# koszulka_led.net
KiCad netlist of a schematic drawn in EAGLE
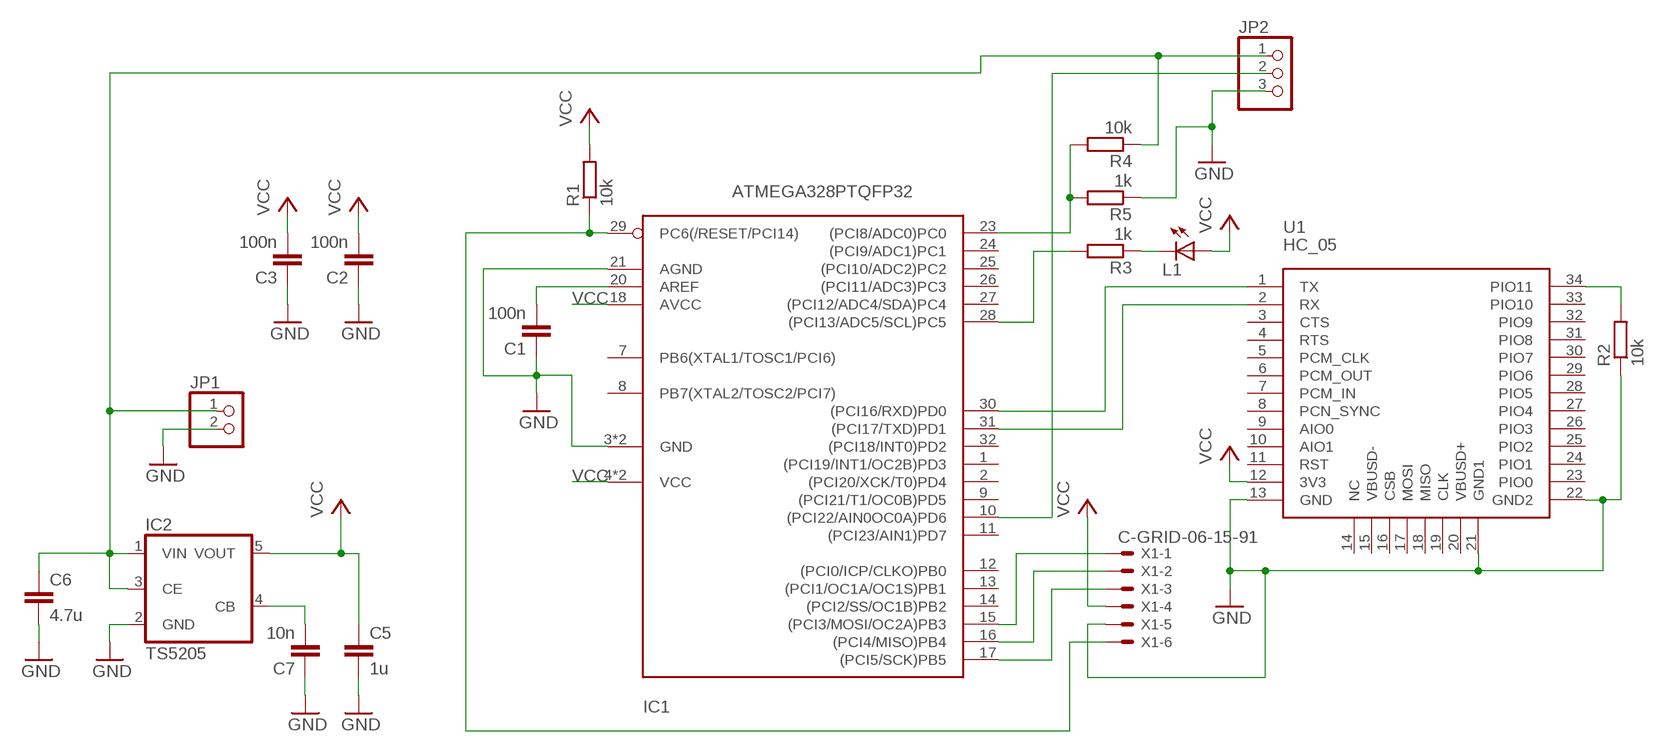
[diagram p0: schematic, sheet 1]

(export (version "E")
  (design (tool "Eeschema 10.0.6"))
  (components
    (comp (ref "C1")
      (value "100n")
      (footprint "eagle-import:C0402")
      (libsource (lib "eagle-import") (part "C-EUC0402"))
    )
    (comp (ref "C2")
      (value "100n")
      (footprint "eagle-import:C0402")
      (libsource (lib "eagle-import") (part "C-EUC0402"))
    )
    (comp (ref "C3")
      (value "100n")
      (footprint "eagle-import:C0402")
      (libsource (lib "eagle-import") (part "C-EUC0402"))
    )
    (comp (ref "C5")
      (value "1u")
      (footprint "eagle-import:C0805")
      (libsource (lib "eagle-import") (part "C-EUC0805"))
    )
    (comp (ref "C6")
      (value "4.7u")
      (footprint "eagle-import:C0805")
      (libsource (lib "eagle-import") (part "C-EUC0805"))
    )
    (comp (ref "C7")
      (value "10n")
      (footprint "eagle-import:C0402")
      (libsource (lib "eagle-import") (part "C-EUC0402"))
    )
    (comp (ref "IC1")
      (value "ATMEGA328PTQFP32")
      (footprint "eagle-import:TQFP32-08")
      (libsource (lib "eagle-import") (part "ATMEGA328PTQFP32"))
    )
    (comp (ref "IC2")
      (value "TS5205")
      (footprint "eagle-import:SOT25")
      (libsource (lib "eagle-import") (part "TS5205"))
    )
    (comp (ref "JP1")
      (value "PINHD-1X2")
      (footprint "eagle-import:1X02")
      (libsource (lib "eagle-import") (part "PINHD-1X2"))
    )
    (comp (ref "JP2")
      (value "PINHD-1X3")
      (footprint "eagle-import:1X03")
      (libsource (lib "eagle-import") (part "PINHD-1X3"))
    )
    (comp (ref "L1")
      (value "LEDCHIP-LED0603")
      (footprint "eagle-import:CHIP-LED0603")
      (libsource (lib "eagle-import") (part "LEDCHIP-LED0603"))
    )
    (comp (ref "R1")
      (value "10k")
      (footprint "eagle-import:R0603")
      (libsource (lib "eagle-import") (part "R-EU_R0603"))
    )
    (comp (ref "R2")
      (value "10k")
      (footprint "eagle-import:R0603")
      (libsource (lib "eagle-import") (part "R-EU_R0603"))
    )
    (comp (ref "R3")
      (value "1k")
      (footprint "eagle-import:R0603")
      (libsource (lib "eagle-import") (part "R-EU_R0603"))
    )
    (comp (ref "R4")
      (value "10k")
      (footprint "eagle-import:R0603")
      (libsource (lib "eagle-import") (part "R-EU_R0603"))
    )
    (comp (ref "R5")
      (value "1k")
      (footprint "eagle-import:R0603")
      (libsource (lib "eagle-import") (part "R-EU_R0603"))
    )
    (comp (ref "U1")
      (value "HC_05")
      (footprint "eagle-import:BLUETOOTH_SMD")
      (libsource (lib "eagle-import") (part "HC_05"))
    )
    (comp (ref "X1")
      (value "C-GRID-06-15-91")
      (footprint "eagle-import:15-91-06")
      (libsource (lib "eagle-import") (part "C-GRID-06-15-91"))
    )
  )
  (nets
    (net (code "1") (name "GND") (class "Default")
      (node (ref "C1") (pin "1") (pinfunction "1_1") (pintype "passive"))
      (node (ref "C2") (pin "1") (pinfunction "1_1") (pintype "passive"))
      (node (ref "C3") (pin "1") (pinfunction "1_1") (pintype "passive"))
      (node (ref "C5") (pin "2") (pinfunction "2_2") (pintype "passive"))
      (node (ref "C6") (pin "2") (pinfunction "2_2") (pintype "passive"))
      (node (ref "C7") (pin "1") (pinfunction "1_1") (pintype "passive"))
      (node (ref "IC1") (pin "21") (pinfunction "AGND_21") (pintype "bidirectional"))
      (node (ref "IC1") (pin "3") (pinfunction "GND_3") (pintype "bidirectional"))
      (node (ref "IC1") (pin "5") (pinfunction "GND_5") (pintype "bidirectional"))
      (node (ref "IC2") (pin "2") (pinfunction "GND_2") (pintype "passive"))
      (node (ref "JP1") (pin "2") (pinfunction "2_2") (pintype "passive"))
      (node (ref "JP2") (pin "3") (pinfunction "3_3") (pintype "passive"))
      (node (ref "R2") (pin "1") (pinfunction "1_1") (pintype "passive"))
      (node (ref "R5") (pin "1") (pinfunction "1_1") (pintype "passive"))
      (node (ref "U1") (pin "13") (pinfunction "GND_13") (pintype "bidirectional"))
      (node (ref "U1") (pin "21") (pinfunction "GND1_21") (pintype "bidirectional"))
      (node (ref "U1") (pin "22") (pinfunction "GND2_22") (pintype "bidirectional"))
      (node (ref "X1") (pin "5") (pinfunction "S_5") (pintype "passive"))
    )
    (net (code "2") (name "Net-(IC1-(PCI3{slash}MOSI{slash}OC2A)PB3)") (class "Default")
      (node (ref "IC1") (pin "15") (pinfunction "(PCI3/MOSI/OC2A)PB3_15") (pintype "bidirectional"))
      (node (ref "X1") (pin "1") (pinfunction "S_1") (pintype "passive"))
    )
    (net (code "3") (name "Net-(IC1-(PCI4{slash}MISO)PB4)") (class "Default")
      (node (ref "IC1") (pin "16") (pinfunction "(PCI4/MISO)PB4_16") (pintype "bidirectional"))
      (node (ref "X1") (pin "2") (pinfunction "S_2") (pintype "passive"))
    )
    (net (code "4") (name "Net-(IC1-(PCI5{slash}SCK)PB5)") (class "Default")
      (node (ref "IC1") (pin "17") (pinfunction "(PCI5/SCK)PB5_17") (pintype "bidirectional"))
      (node (ref "X1") (pin "3") (pinfunction "S_3") (pintype "passive"))
    )
    (net (code "5") (name "Net-(IC1-(PCI8{slash}ADC0)PC0)") (class "Default")
      (node (ref "IC1") (pin "23") (pinfunction "(PCI8/ADC0)PC0_23") (pintype "bidirectional"))
      (node (ref "R4") (pin "2") (pinfunction "2_2") (pintype "passive"))
      (node (ref "R5") (pin "2") (pinfunction "2_2") (pintype "passive"))
    )
    (net (code "6") (name "Net-(IC1-(PCI13{slash}ADC5{slash}SCL)PC5)") (class "Default")
      (node (ref "IC1") (pin "28") (pinfunction "(PCI13/ADC5/SCL)PC5_28") (pintype "bidirectional"))
      (node (ref "R3") (pin "2") (pinfunction "2_2") (pintype "passive"))
    )
    (net (code "7") (name "Net-(IC1-(PCI16{slash}RXD)PD0)") (class "Default")
      (node (ref "IC1") (pin "30") (pinfunction "(PCI16/RXD)PD0_30") (pintype "bidirectional"))
      (node (ref "U1") (pin "1") (pinfunction "TX_1") (pintype "bidirectional"))
    )
    (net (code "8") (name "Net-(IC1-(PCI17{slash}TXD)PD1)") (class "Default")
      (node (ref "IC1") (pin "31") (pinfunction "(PCI17/TXD)PD1_31") (pintype "bidirectional"))
      (node (ref "U1") (pin "2") (pinfunction "RX_2") (pintype "bidirectional"))
    )
    (net (code "9") (name "Net-(IC1-(PCI22{slash}AIN0OC0A)PD6)") (class "Default")
      (node (ref "IC1") (pin "10") (pinfunction "(PCI22/AIN0OC0A)PD6_10") (pintype "bidirectional"))
      (node (ref "JP2") (pin "2") (pinfunction "2_2") (pintype "passive"))
    )
    (net (code "10") (name "Net-(IC1-AREF)") (class "Default")
      (node (ref "C1") (pin "2") (pinfunction "2_2") (pintype "passive"))
      (node (ref "IC1") (pin "20") (pinfunction "AREF_20") (pintype "bidirectional"))
    )
    (net (code "11") (name "Net-(IC1-PC6({slash}RESET{slash}PCI14))") (class "Default")
      (node (ref "IC1") (pin "29") (pinfunction "PC6(/RESET/PCI14)_29") (pintype "bidirectional"))
      (node (ref "R1") (pin "1") (pinfunction "1_1") (pintype "passive"))
      (node (ref "X1") (pin "6") (pinfunction "S_6") (pintype "passive"))
    )
    (net (code "12") (name "Net-(IC2-CB)") (class "Default")
      (node (ref "C7") (pin "2") (pinfunction "2_2") (pintype "passive"))
      (node (ref "IC2") (pin "4") (pinfunction "CB_4") (pintype "input"))
    )
    (net (code "13") (name "Net-(IC2-CE)") (class "Default")
      (node (ref "C6") (pin "1") (pinfunction "1_1") (pintype "passive"))
      (node (ref "IC2") (pin "1") (pinfunction "VIN_1") (pintype "input"))
      (node (ref "IC2") (pin "3") (pinfunction "CE_3") (pintype "input"))
      (node (ref "JP1") (pin "1") (pinfunction "1_1") (pintype "passive"))
      (node (ref "JP2") (pin "1") (pinfunction "1_1") (pintype "passive"))
      (node (ref "R4") (pin "1") (pinfunction "1_1") (pintype "passive"))
    )
    (net (code "14") (name "Net-(L1-PadC)") (class "Default")
      (node (ref "L1") (pin "C") (pinfunction "C_C") (pintype "passive"))
      (node (ref "R3") (pin "1") (pinfunction "1_1") (pintype "passive"))
    )
    (net (code "15") (name "Net-(U1-PIO11)") (class "Default")
      (node (ref "R2") (pin "2") (pinfunction "2_2") (pintype "passive"))
      (node (ref "U1") (pin "34") (pinfunction "PIO11_34") (pintype "bidirectional"))
    )
    (net (code "16") (name "VCC") (class "Default")
      (node (ref "C2") (pin "2") (pinfunction "2_2") (pintype "passive"))
      (node (ref "C3") (pin "2") (pinfunction "2_2") (pintype "passive"))
      (node (ref "C5") (pin "1") (pinfunction "1_1") (pintype "passive"))
      (node (ref "IC1") (pin "18") (pinfunction "AVCC_18") (pintype "bidirectional"))
      (node (ref "IC1") (pin "4") (pinfunction "VCC_4") (pintype "bidirectional"))
      (node (ref "IC1") (pin "6") (pinfunction "VCC_6") (pintype "bidirectional"))
      (node (ref "IC2") (pin "5") (pinfunction "VOUT_5") (pintype "passive"))
      (node (ref "L1") (pin "A") (pinfunction "A_A") (pintype "passive"))
      (node (ref "R1") (pin "2") (pinfunction "2_2") (pintype "passive"))
      (node (ref "U1") (pin "12") (pinfunction "3V3_12") (pintype "bidirectional"))
      (node (ref "X1") (pin "4") (pinfunction "S_4") (pintype "passive"))
    )
    (net (code "17") (name "unconnected-(IC1-(PCI0{slash}ICP{slash}CLKO)PB0-Pad12)") (class "Default")
      (node (ref "IC1") (pin "12") (pinfunction "(PCI0/ICP/CLKO)PB0_12") (pintype "bidirectional"))
    )
    (net (code "18") (name "unconnected-(IC1-(PCI1{slash}OC1A{slash}OC1S)PB1-Pad13)") (class "Default")
      (node (ref "IC1") (pin "13") (pinfunction "(PCI1/OC1A/OC1S)PB1_13") (pintype "bidirectional"))
    )
    (net (code "19") (name "unconnected-(IC1-(PCI2{slash}SS{slash}OC1B)PB2-Pad14)") (class "Default")
      (node (ref "IC1") (pin "14") (pinfunction "(PCI2/SS/OC1B)PB2_14") (pintype "bidirectional"))
    )
    (net (code "20") (name "unconnected-(IC1-(PCI9{slash}ADC1)PC1-Pad24)") (class "Default")
      (node (ref "IC1") (pin "24") (pinfunction "(PCI9/ADC1)PC1_24") (pintype "bidirectional"))
    )
    (net (code "21") (name "unconnected-(IC1-(PCI10{slash}ADC2)PC2-Pad25)") (class "Default")
      (node (ref "IC1") (pin "25") (pinfunction "(PCI10/ADC2)PC2_25") (pintype "bidirectional"))
    )
    (net (code "22") (name "unconnected-(IC1-(PCI11{slash}ADC3)PC3-Pad26)") (class "Default")
      (node (ref "IC1") (pin "26") (pinfunction "(PCI11/ADC3)PC3_26") (pintype "bidirectional"))
    )
    (net (code "23") (name "unconnected-(IC1-(PCI12{slash}ADC4{slash}SDA)PC4-Pad27)") (class "Default")
      (node (ref "IC1") (pin "27") (pinfunction "(PCI12/ADC4/SDA)PC4_27") (pintype "bidirectional"))
    )
    (net (code "24") (name "unconnected-(IC1-(PCI18{slash}INT0)PD2-Pad32)") (class "Default")
      (node (ref "IC1") (pin "32") (pinfunction "(PCI18/INT0)PD2_32") (pintype "bidirectional"))
    )
    (net (code "25") (name "unconnected-(IC1-(PCI19{slash}INT1{slash}OC2B)PD3-Pad1)") (class "Default")
      (node (ref "IC1") (pin "1") (pinfunction "(PCI19/INT1/OC2B)PD3_1") (pintype "bidirectional"))
    )
    (net (code "26") (name "unconnected-(IC1-(PCI20{slash}XCK{slash}T0)PD4-Pad2)") (class "Default")
      (node (ref "IC1") (pin "2") (pinfunction "(PCI20/XCK/T0)PD4_2") (pintype "bidirectional"))
    )
    (net (code "27") (name "unconnected-(IC1-(PCI21{slash}T1{slash}OC0B)PD5-Pad9)") (class "Default")
      (node (ref "IC1") (pin "9") (pinfunction "(PCI21/T1/OC0B)PD5_9") (pintype "bidirectional"))
    )
    (net (code "28") (name "unconnected-(IC1-(PCI23{slash}AIN1)PD7-Pad11)") (class "Default")
      (node (ref "IC1") (pin "11") (pinfunction "(PCI23/AIN1)PD7_11") (pintype "bidirectional"))
    )
    (net (code "29") (name "unconnected-(IC1-PB6(XTAL1{slash}TOSC1{slash}PCI6)-Pad7)") (class "Default")
      (node (ref "IC1") (pin "7") (pinfunction "PB6(XTAL1/TOSC1/PCI6)_7") (pintype "bidirectional"))
    )
    (net (code "30") (name "unconnected-(IC1-PB7(XTAL2{slash}TOSC2{slash}PCI7)-Pad8)") (class "Default")
      (node (ref "IC1") (pin "8") (pinfunction "PB7(XTAL2/TOSC2/PCI7)_8") (pintype "bidirectional"))
    )
    (net (code "31") (name "unconnected-(U1-AIO0-Pad9)") (class "Default")
      (node (ref "U1") (pin "9") (pinfunction "AIO0_9") (pintype "bidirectional"))
    )
    (net (code "32") (name "unconnected-(U1-AIO1-Pad10)") (class "Default")
      (node (ref "U1") (pin "10") (pinfunction "AIO1_10") (pintype "bidirectional"))
    )
    (net (code "33") (name "unconnected-(U1-CLK-Pad19)") (class "Default")
      (node (ref "U1") (pin "19") (pinfunction "CLK_19") (pintype "bidirectional"))
    )
    (net (code "34") (name "unconnected-(U1-CSB-Pad16)") (class "Default")
      (node (ref "U1") (pin "16") (pinfunction "CSB_16") (pintype "bidirectional"))
    )
    (net (code "35") (name "unconnected-(U1-CTS-Pad3)") (class "Default")
      (node (ref "U1") (pin "3") (pinfunction "CTS_3") (pintype "bidirectional"))
    )
    (net (code "36") (name "unconnected-(U1-MISO-Pad18)") (class "Default")
      (node (ref "U1") (pin "18") (pinfunction "MISO_18") (pintype "bidirectional"))
    )
    (net (code "37") (name "unconnected-(U1-MOSI-Pad17)") (class "Default")
      (node (ref "U1") (pin "17") (pinfunction "MOSI_17") (pintype "bidirectional"))
    )
    (net (code "38") (name "unconnected-(U1-NC-Pad14)") (class "Default")
      (node (ref "U1") (pin "14") (pinfunction "NC_14") (pintype "bidirectional"))
    )
    (net (code "39") (name "unconnected-(U1-PCM_CLK-Pad5)") (class "Default")
      (node (ref "U1") (pin "5") (pinfunction "PCM_CLK_5") (pintype "bidirectional"))
    )
    (net (code "40") (name "unconnected-(U1-PCM_IN-Pad7)") (class "Default")
      (node (ref "U1") (pin "7") (pinfunction "PCM_IN_7") (pintype "bidirectional"))
    )
    (net (code "41") (name "unconnected-(U1-PCM_OUT-Pad6)") (class "Default")
      (node (ref "U1") (pin "6") (pinfunction "PCM_OUT_6") (pintype "bidirectional"))
    )
    (net (code "42") (name "unconnected-(U1-PCN_SYNC-Pad8)") (class "Default")
      (node (ref "U1") (pin "8") (pinfunction "PCN_SYNC_8") (pintype "bidirectional"))
    )
    (net (code "43") (name "unconnected-(U1-PIO0-Pad23)") (class "Default")
      (node (ref "U1") (pin "23") (pinfunction "PIO0_23") (pintype "bidirectional"))
    )
    (net (code "44") (name "unconnected-(U1-PIO1-Pad24)") (class "Default")
      (node (ref "U1") (pin "24") (pinfunction "PIO1_24") (pintype "bidirectional"))
    )
    (net (code "45") (name "unconnected-(U1-PIO2-Pad25)") (class "Default")
      (node (ref "U1") (pin "25") (pinfunction "PIO2_25") (pintype "bidirectional"))
    )
    (net (code "46") (name "unconnected-(U1-PIO3-Pad26)") (class "Default")
      (node (ref "U1") (pin "26") (pinfunction "PIO3_26") (pintype "bidirectional"))
    )
    (net (code "47") (name "unconnected-(U1-PIO4-Pad27)") (class "Default")
      (node (ref "U1") (pin "27") (pinfunction "PIO4_27") (pintype "bidirectional"))
    )
    (net (code "48") (name "unconnected-(U1-PIO5-Pad28)") (class "Default")
      (node (ref "U1") (pin "28") (pinfunction "PIO5_28") (pintype "bidirectional"))
    )
    (net (code "49") (name "unconnected-(U1-PIO6-Pad29)") (class "Default")
      (node (ref "U1") (pin "29") (pinfunction "PIO6_29") (pintype "bidirectional"))
    )
    (net (code "50") (name "unconnected-(U1-PIO7-Pad30)") (class "Default")
      (node (ref "U1") (pin "30") (pinfunction "PIO7_30") (pintype "bidirectional"))
    )
    (net (code "51") (name "unconnected-(U1-PIO8-Pad31)") (class "Default")
      (node (ref "U1") (pin "31") (pinfunction "PIO8_31") (pintype "bidirectional"))
    )
    (net (code "52") (name "unconnected-(U1-PIO9-Pad32)") (class "Default")
      (node (ref "U1") (pin "32") (pinfunction "PIO9_32") (pintype "bidirectional"))
    )
    (net (code "53") (name "unconnected-(U1-PIO10-Pad33)") (class "Default")
      (node (ref "U1") (pin "33") (pinfunction "PIO10_33") (pintype "bidirectional"))
    )
    (net (code "54") (name "unconnected-(U1-RST-Pad11)") (class "Default")
      (node (ref "U1") (pin "11") (pinfunction "RST_11") (pintype "bidirectional"))
    )
    (net (code "55") (name "unconnected-(U1-RTS-Pad4)") (class "Default")
      (node (ref "U1") (pin "4") (pinfunction "RTS_4") (pintype "bidirectional"))
    )
    (net (code "56") (name "unconnected-(U1-VBUSD+-Pad20)") (class "Default")
      (node (ref "U1") (pin "20") (pinfunction "VBUSD+_20") (pintype "bidirectional"))
    )
    (net (code "57") (name "unconnected-(U1-VBUSD--Pad15)") (class "Default")
      (node (ref "U1") (pin "15") (pinfunction "VBUSD-_15") (pintype "bidirectional"))
    )
  )
)
